# One_Square_Boy.net
KiCad netlist of a schematic drawn in EAGLE
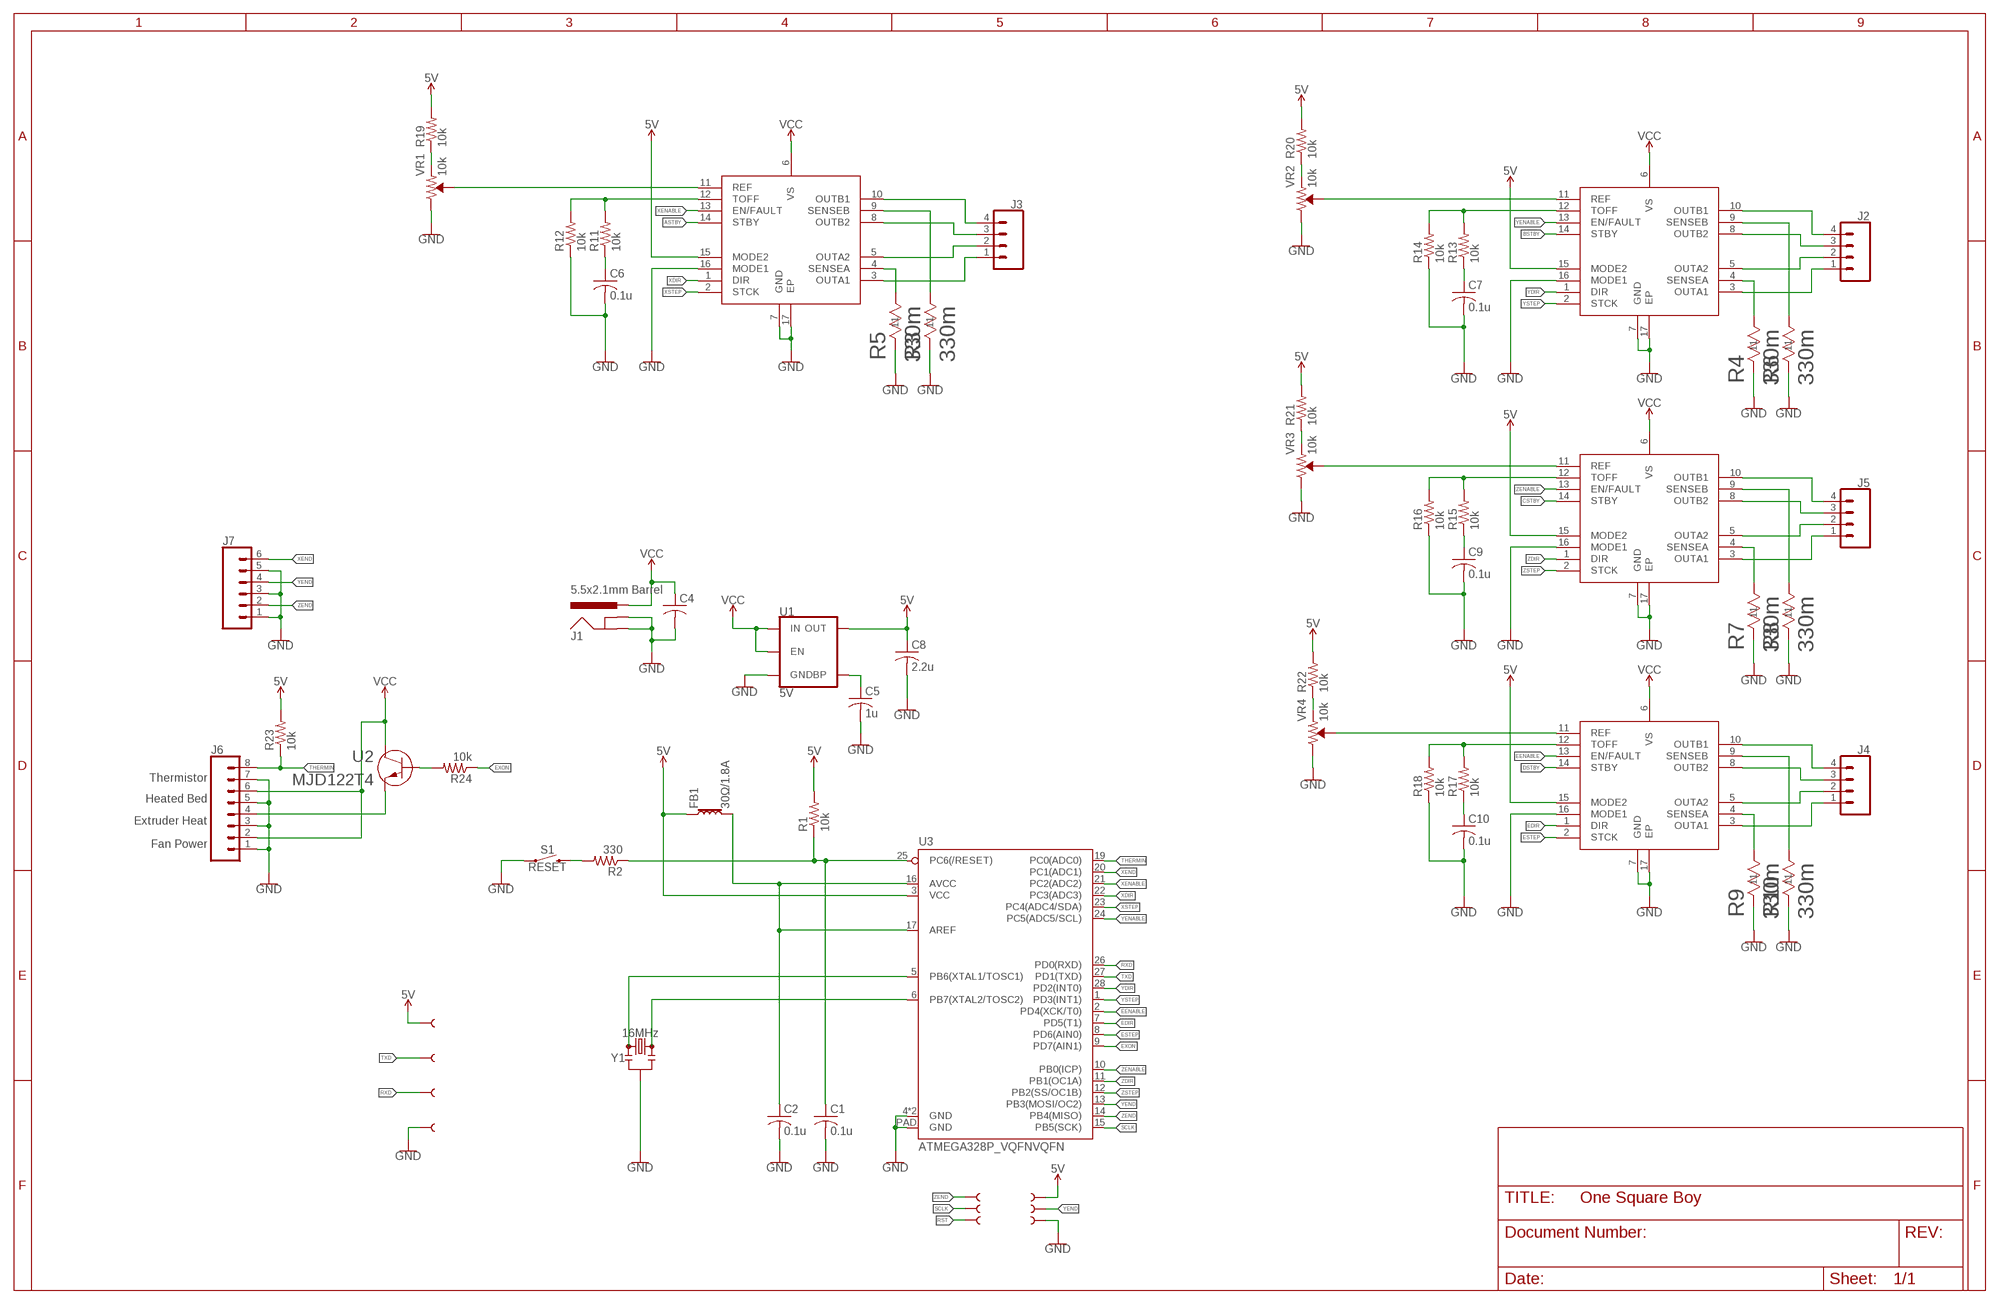
[diagram p0: schematic, sheet 1]

(export (version "E")
  (design (tool "Eeschema 10.0.6"))
  (components
    (comp (ref "C1")
      (value "0.1u")
      (footprint "eagle-import:C0402")
      (libsource (lib "eagle-import") (part "C-USC0402"))
    )
    (comp (ref "C2")
      (value "0.1u")
      (footprint "eagle-import:C0402")
      (libsource (lib "eagle-import") (part "C-USC0402"))
    )
    (comp (ref "C4")
      (value "C-USC1206")
      (footprint "eagle-import:C1206")
      (libsource (lib "eagle-import") (part "C-USC1206"))
    )
    (comp (ref "C5")
      (value "1u")
      (footprint "eagle-import:C0402")
      (libsource (lib "eagle-import") (part "C-USC0402"))
    )
    (comp (ref "C6")
      (value "0.1u")
      (footprint "eagle-import:C0402")
      (libsource (lib "eagle-import") (part "C-USC0402"))
    )
    (comp (ref "C7")
      (value "0.1u")
      (footprint "eagle-import:C0402")
      (libsource (lib "eagle-import") (part "C-USC0402"))
    )
    (comp (ref "C8")
      (value "2.2u")
      (footprint "eagle-import:C0402")
      (libsource (lib "eagle-import") (part "C-USC0402"))
    )
    (comp (ref "C9")
      (value "0.1u")
      (footprint "eagle-import:C0402")
      (libsource (lib "eagle-import") (part "C-USC0402"))
    )
    (comp (ref "C10")
      (value "0.1u")
      (footprint "eagle-import:C0402")
      (libsource (lib "eagle-import") (part "C-USC0402"))
    )
    (comp (ref "FB1")
      (value "30Ω/1.8A")
      (footprint "eagle-import:0603")
      (libsource (lib "eagle-import") (part "FERRITE_BEAD-0603"))
    )
    (comp (ref "J1")
      (value "5.5x2.1mm Barrel")
      (footprint "eagle-import:POWER_JACK_SMD")
      (libsource (lib "eagle-import") (part "POWER_JACKSMD"))
    )
    (comp (ref "J2")
      (value "CONN_04SMD2")
      (footprint "eagle-import:1X04_1MM_RA")
      (libsource (lib "eagle-import") (part "CONN_04SMD2"))
    )
    (comp (ref "J3")
      (value "CONN_04SMD2")
      (footprint "eagle-import:1X04_1MM_RA")
      (libsource (lib "eagle-import") (part "CONN_04SMD2"))
    )
    (comp (ref "J4")
      (value "CONN_04SMD2")
      (footprint "eagle-import:1X04_1MM_RA")
      (libsource (lib "eagle-import") (part "CONN_04SMD2"))
    )
    (comp (ref "J5")
      (value "CONN_04SMD2")
      (footprint "eagle-import:1X04_1MM_RA")
      (libsource (lib "eagle-import") (part "CONN_04SMD2"))
    )
    (comp (ref "J6")
      (value "CONN_08BM08B-SRSS-TB")
      (footprint "eagle-import:BM08B-SRSS-TB")
      (libsource (lib "eagle-import") (part "CONN_08BM08B-SRSS-TB"))
    )
    (comp (ref "J7")
      (value "CONN_06SMD-1MM")
      (footprint "eagle-import:1X06-1MM")
      (libsource (lib "eagle-import") (part "CONN_06SMD-1MM"))
    )
    (comp (ref "R1")
      (value "10k")
      (footprint "eagle-import:R0402")
      (libsource (lib "eagle-import") (part "R-US_R0402"))
    )
    (comp (ref "R2")
      (value "330")
      (footprint "eagle-import:R0402")
      (libsource (lib "eagle-import") (part "R-US_R0402"))
    )
    (comp (ref "R3")
      (value "330m")
      (footprint "eagle-import:RES_2012-L")
      (fields (field (name "MANUFACTURER_PART_NUMBER") "KRL2012EMR330FT5"))
      (libsource (lib "eagle-import") (part "KRL2012E-M-R330-F-T5RES_2012-L"))
    )
    (comp (ref "R4")
      (value "330m")
      (footprint "eagle-import:RES_2012-L")
      (fields (field (name "MANUFACTURER_PART_NUMBER") "KRL2012EMR330FT5"))
      (libsource (lib "eagle-import") (part "KRL2012E-M-R330-F-T5RES_2012-L"))
    )
    (comp (ref "R5")
      (value "330m")
      (footprint "eagle-import:RES_2012-L")
      (fields (field (name "MANUFACTURER_PART_NUMBER") "KRL2012EMR330FT5"))
      (libsource (lib "eagle-import") (part "KRL2012E-M-R330-F-T5RES_2012-L"))
    )
    (comp (ref "R6")
      (value "330m")
      (footprint "eagle-import:RES_2012-L")
      (fields (field (name "MANUFACTURER_PART_NUMBER") "KRL2012EMR330FT5"))
      (libsource (lib "eagle-import") (part "KRL2012E-M-R330-F-T5RES_2012-L"))
    )
    (comp (ref "R7")
      (value "330m")
      (footprint "eagle-import:RES_2012-L")
      (fields (field (name "MANUFACTURER_PART_NUMBER") "KRL2012EMR330FT5"))
      (libsource (lib "eagle-import") (part "KRL2012E-M-R330-F-T5RES_2012-L"))
    )
    (comp (ref "R8")
      (value "330m")
      (footprint "eagle-import:RES_2012-L")
      (fields (field (name "MANUFACTURER_PART_NUMBER") "KRL2012EMR330FT5"))
      (libsource (lib "eagle-import") (part "KRL2012E-M-R330-F-T5RES_2012-L"))
    )
    (comp (ref "R9")
      (value "330m")
      (footprint "eagle-import:RES_2012-L")
      (fields (field (name "MANUFACTURER_PART_NUMBER") "KRL2012EMR330FT5"))
      (libsource (lib "eagle-import") (part "KRL2012E-M-R330-F-T5RES_2012-L"))
    )
    (comp (ref "R10")
      (value "330m")
      (footprint "eagle-import:RES_2012-L")
      (fields (field (name "MANUFACTURER_PART_NUMBER") "KRL2012EMR330FT5"))
      (libsource (lib "eagle-import") (part "KRL2012E-M-R330-F-T5RES_2012-L"))
    )
    (comp (ref "R11")
      (value "10k")
      (footprint "eagle-import:R0402")
      (libsource (lib "eagle-import") (part "R-US_R0402"))
    )
    (comp (ref "R12")
      (value "10k")
      (footprint "eagle-import:R0402")
      (libsource (lib "eagle-import") (part "R-US_R0402"))
    )
    (comp (ref "R13")
      (value "10k")
      (footprint "eagle-import:R0402")
      (libsource (lib "eagle-import") (part "R-US_R0402"))
    )
    (comp (ref "R14")
      (value "10k")
      (footprint "eagle-import:R0402")
      (libsource (lib "eagle-import") (part "R-US_R0402"))
    )
    (comp (ref "R15")
      (value "10k")
      (footprint "eagle-import:R0402")
      (libsource (lib "eagle-import") (part "R-US_R0402"))
    )
    (comp (ref "R16")
      (value "10k")
      (footprint "eagle-import:R0402")
      (libsource (lib "eagle-import") (part "R-US_R0402"))
    )
    (comp (ref "R17")
      (value "10k")
      (footprint "eagle-import:R0402")
      (libsource (lib "eagle-import") (part "R-US_R0402"))
    )
    (comp (ref "R18")
      (value "10k")
      (footprint "eagle-import:R0402")
      (libsource (lib "eagle-import") (part "R-US_R0402"))
    )
    (comp (ref "R19")
      (value "10k")
      (footprint "eagle-import:R0402")
      (libsource (lib "eagle-import") (part "R-US_R0402"))
    )
    (comp (ref "R20")
      (value "10k")
      (footprint "eagle-import:R0402")
      (libsource (lib "eagle-import") (part "R-US_R0402"))
    )
    (comp (ref "R21")
      (value "10k")
      (footprint "eagle-import:R0402")
      (libsource (lib "eagle-import") (part "R-US_R0402"))
    )
    (comp (ref "R22")
      (value "10k")
      (footprint "eagle-import:R0402")
      (libsource (lib "eagle-import") (part "R-US_R0402"))
    )
    (comp (ref "R23")
      (value "10k")
      (footprint "eagle-import:R0402")
      (libsource (lib "eagle-import") (part "R-US_R0402"))
    )
    (comp (ref "R24")
      (value "10k")
      (footprint "eagle-import:R0402")
      (libsource (lib "eagle-import") (part "R-US_R0402"))
    )
    (comp (ref "S1")
      (value "RESET")
      (footprint "eagle-import:TACTILE_SWITCH_SMD_4.6X2.8MM")
      (libsource (lib "eagle-import") (part "MOMENTARY-SWITCH-SPST-SMD-4.6X2.8MM"))
    )
    (comp (ref "TP1")
      (value "TEST-POINT3X5")
      (footprint "eagle-import:PAD.03X.05")
      (libsource (lib "eagle-import") (part "TEST-POINT3X5"))
    )
    (comp (ref "TP2")
      (value "TEST-POINT3X5")
      (footprint "eagle-import:PAD.03X.05")
      (libsource (lib "eagle-import") (part "TEST-POINT3X5"))
    )
    (comp (ref "TP3")
      (value "TEST-POINT3X5")
      (footprint "eagle-import:PAD.03X.05")
      (libsource (lib "eagle-import") (part "TEST-POINT3X5"))
    )
    (comp (ref "TP4")
      (value "TEST-POINT3X5")
      (footprint "eagle-import:PAD.03X.05")
      (libsource (lib "eagle-import") (part "TEST-POINT3X5"))
    )
    (comp (ref "TP5")
      (value "TEST-POINT3X5")
      (footprint "eagle-import:PAD.03X.05")
      (libsource (lib "eagle-import") (part "TEST-POINT3X5"))
    )
    (comp (ref "TP6")
      (value "TEST-POINT3X5")
      (footprint "eagle-import:PAD.03X.05")
      (libsource (lib "eagle-import") (part "TEST-POINT3X5"))
    )
    (comp (ref "TP7")
      (value "TEST-POINT3X5")
      (footprint "eagle-import:PAD.03X.05")
      (libsource (lib "eagle-import") (part "TEST-POINT3X5"))
    )
    (comp (ref "TP8")
      (value "TEST-POINT3X5")
      (footprint "eagle-import:PAD.03X.05")
      (libsource (lib "eagle-import") (part "TEST-POINT3X5"))
    )
    (comp (ref "TP9")
      (value "TEST-POINT3X5")
      (footprint "eagle-import:PAD.03X.05")
      (libsource (lib "eagle-import") (part "TEST-POINT3X5"))
    )
    (comp (ref "TP10")
      (value "TEST-POINT3X5")
      (footprint "eagle-import:PAD.03X.05")
      (libsource (lib "eagle-import") (part "TEST-POINT3X5"))
    )
    (comp (ref "U$1")
      (value "STSPIN220")
      (footprint "eagle-import:QFN50P300X300X100-17N")
      (libsource (lib "eagle-import") (part "STSPIN220"))
    )
    (comp (ref "U$2")
      (value "STSPIN220")
      (footprint "eagle-import:QFN50P300X300X100-17N")
      (libsource (lib "eagle-import") (part "STSPIN220"))
    )
    (comp (ref "U$3")
      (value "STSPIN220")
      (footprint "eagle-import:QFN50P300X300X100-17N")
      (libsource (lib "eagle-import") (part "STSPIN220"))
    )
    (comp (ref "U$4")
      (value "STSPIN220")
      (footprint "eagle-import:QFN50P300X300X100-17N")
      (libsource (lib "eagle-import") (part "STSPIN220"))
    )
    (comp (ref "U1")
      (value "5V")
      (footprint "eagle-import:SOT23-5")
      (libsource (lib "eagle-import") (part "V_REG_MIC52055V"))
    )
    (comp (ref "U2")
      (value "MJD122T4")
      (footprint "eagle-import:DPAK")
      (libsource (lib "eagle-import") (part "MJD122T4"))
    )
    (comp (ref "U3")
      (value "ATMEGA328P_VQFNVQFN")
      (footprint "eagle-import:VQFN-28")
      (libsource (lib "eagle-import") (part "ATMEGA328P_VQFNVQFN"))
    )
    (comp (ref "VR1")
      (value "10k")
      (footprint "eagle-import:TRIMPOT-SMD-TC33X")
      (libsource (lib "eagle-import") (part "TRIMPOT-SMD-3MM-OPEN-1/10W-25%"))
    )
    (comp (ref "VR2")
      (value "10k")
      (footprint "eagle-import:TRIMPOT-SMD-TC33X")
      (libsource (lib "eagle-import") (part "TRIMPOT-SMD-3MM-OPEN-1/10W-25%"))
    )
    (comp (ref "VR3")
      (value "10k")
      (footprint "eagle-import:TRIMPOT-SMD-TC33X")
      (libsource (lib "eagle-import") (part "TRIMPOT-SMD-3MM-OPEN-1/10W-25%"))
    )
    (comp (ref "VR4")
      (value "10k")
      (footprint "eagle-import:TRIMPOT-SMD-TC33X")
      (libsource (lib "eagle-import") (part "TRIMPOT-SMD-3MM-OPEN-1/10W-25%"))
    )
    (comp (ref "Y1")
      (value "16MHz")
      (footprint "eagle-import:RESONATOR-SMD-3.2X1.3")
      (libsource (lib "eagle-import") (part "RESONATOR-16MHZSMD_3.2X1.3"))
    )
  )
  (nets
    (net (code "1") (name "5V") (class "Default")
      (node (ref "C8") (pin "1") (pinfunction "1_1") (pintype "passive"))
      (node (ref "FB1") (pin "1") (pinfunction "1_1") (pintype "passive"))
      (node (ref "R1") (pin "2") (pinfunction "2_2") (pintype "passive"))
      (node (ref "R19") (pin "2") (pinfunction "2_2") (pintype "passive"))
      (node (ref "R20") (pin "2") (pinfunction "2_2") (pintype "passive"))
      (node (ref "R21") (pin "2") (pinfunction "2_2") (pintype "passive"))
      (node (ref "R22") (pin "2") (pinfunction "2_2") (pintype "passive"))
      (node (ref "R23") (pin "2") (pinfunction "2_2") (pintype "passive"))
      (node (ref "TP10") (pin "P$1") (pinfunction "1_P$1") (pintype "bidirectional"))
      (node (ref "TP4") (pin "P$1") (pinfunction "1_P$1") (pintype "bidirectional"))
      (node (ref "U$1") (pin "15") (pinfunction "MODE2_15") (pintype "bidirectional"))
      (node (ref "U$2") (pin "15") (pinfunction "MODE2_15") (pintype "bidirectional"))
      (node (ref "U$3") (pin "15") (pinfunction "MODE2_15") (pintype "bidirectional"))
      (node (ref "U$4") (pin "15") (pinfunction "MODE2_15") (pintype "bidirectional"))
      (node (ref "U1") (pin "5") (pinfunction "OUT_5") (pintype "passive"))
      (node (ref "U3") (pin "3") (pinfunction "VCC_3") (pintype "bidirectional"))
    )
    (net (code "2") (name "ASTBY") (class "Default")
      (node (ref "U$1") (pin "14") (pinfunction "STBY_14") (pintype "bidirectional"))
    )
    (net (code "3") (name "BSTBY") (class "Default")
      (node (ref "U$2") (pin "14") (pinfunction "STBY_14") (pintype "bidirectional"))
    )
    (net (code "4") (name "CSTBY") (class "Default")
      (node (ref "U$3") (pin "14") (pinfunction "STBY_14") (pintype "bidirectional"))
    )
    (net (code "5") (name "DSTBY") (class "Default")
      (node (ref "U$4") (pin "14") (pinfunction "STBY_14") (pintype "bidirectional"))
    )
    (net (code "6") (name "EDIR") (class "Default")
      (node (ref "U$4") (pin "1") (pinfunction "DIR_1") (pintype "bidirectional"))
      (node (ref "U3") (pin "7") (pinfunction "PD5(T1)_7") (pintype "bidirectional"))
    )
    (net (code "7") (name "EENABLE") (class "Default")
      (node (ref "U$4") (pin "13") (pinfunction "EN/FAULT_13") (pintype "bidirectional"))
      (node (ref "U3") (pin "2") (pinfunction "PD4(XCK/T0)_2") (pintype "bidirectional"))
    )
    (net (code "8") (name "ESTEP") (class "Default")
      (node (ref "U$4") (pin "2") (pinfunction "STCK_2") (pintype "bidirectional"))
      (node (ref "U3") (pin "8") (pinfunction "PD6(AIN0)_8") (pintype "bidirectional"))
    )
    (net (code "9") (name "EXON") (class "Default")
      (node (ref "R24") (pin "1") (pinfunction "1_1") (pintype "passive"))
      (node (ref "U3") (pin "9") (pinfunction "PD7(AIN1)_9") (pintype "bidirectional"))
    )
    (net (code "10") (name "GND") (class "Default")
      (node (ref "C1") (pin "2") (pinfunction "2_2") (pintype "passive"))
      (node (ref "C10") (pin "2") (pinfunction "2_2") (pintype "passive"))
      (node (ref "C2") (pin "2") (pinfunction "2_2") (pintype "passive"))
      (node (ref "C4") (pin "2") (pinfunction "2_2") (pintype "passive"))
      (node (ref "C5") (pin "2") (pinfunction "2_2") (pintype "passive"))
      (node (ref "C6") (pin "2") (pinfunction "2_2") (pintype "passive"))
      (node (ref "C7") (pin "2") (pinfunction "2_2") (pintype "passive"))
      (node (ref "C8") (pin "2") (pinfunction "2_2") (pintype "passive"))
      (node (ref "C9") (pin "2") (pinfunction "2_2") (pintype "passive"))
      (node (ref "J1") (pin "GND") (pinfunction "GNDBREAK_GND") (pintype "bidirectional"))
      (node (ref "J1") (pin "P$4") (pinfunction "GND_P$4") (pintype "bidirectional"))
      (node (ref "J6") (pin "1") (pinfunction "1_1") (pintype "passive"))
      (node (ref "J6") (pin "3") (pinfunction "3_3") (pintype "passive"))
      (node (ref "J6") (pin "5") (pinfunction "5_5") (pintype "passive"))
      (node (ref "J6") (pin "7") (pinfunction "7_7") (pintype "passive"))
      (node (ref "J7") (pin "1") (pinfunction "1_1") (pintype "passive"))
      (node (ref "J7") (pin "3") (pinfunction "3_3") (pintype "passive"))
      (node (ref "J7") (pin "5") (pinfunction "5_5") (pintype "passive"))
      (node (ref "R10") (pin "1") (pinfunction "11_1") (pintype "passive"))
      (node (ref "R12") (pin "1") (pinfunction "1_1") (pintype "passive"))
      (node (ref "R14") (pin "1") (pinfunction "1_1") (pintype "passive"))
      (node (ref "R16") (pin "1") (pinfunction "1_1") (pintype "passive"))
      (node (ref "R18") (pin "1") (pinfunction "1_1") (pintype "passive"))
      (node (ref "R3") (pin "1") (pinfunction "11_1") (pintype "passive"))
      (node (ref "R4") (pin "1") (pinfunction "11_1") (pintype "passive"))
      (node (ref "R5") (pin "1") (pinfunction "11_1") (pintype "passive"))
      (node (ref "R6") (pin "1") (pinfunction "11_1") (pintype "passive"))
      (node (ref "R7") (pin "1") (pinfunction "11_1") (pintype "passive"))
      (node (ref "R8") (pin "1") (pinfunction "11_1") (pintype "passive"))
      (node (ref "R9") (pin "1") (pinfunction "11_1") (pintype "passive"))
      (node (ref "S1") (pin "1") (pinfunction "1_1") (pintype "passive"))
      (node (ref "S1") (pin "2") (pinfunction "1_2") (pintype "passive"))
      (node (ref "TP6") (pin "P$1") (pinfunction "1_P$1") (pintype "bidirectional"))
      (node (ref "TP7") (pin "P$1") (pinfunction "1_P$1") (pintype "bidirectional"))
      (node (ref "U$1") (pin "16") (pinfunction "MODE1_16") (pintype "bidirectional"))
      (node (ref "U$1") (pin "17") (pinfunction "EP_17") (pintype "bidirectional"))
      (node (ref "U$1") (pin "7") (pinfunction "GND_7") (pintype "bidirectional"))
      (node (ref "U$2") (pin "16") (pinfunction "MODE1_16") (pintype "bidirectional"))
      (node (ref "U$2") (pin "17") (pinfunction "EP_17") (pintype "bidirectional"))
      (node (ref "U$2") (pin "7") (pinfunction "GND_7") (pintype "bidirectional"))
      (node (ref "U$3") (pin "16") (pinfunction "MODE1_16") (pintype "bidirectional"))
      (node (ref "U$3") (pin "17") (pinfunction "EP_17") (pintype "bidirectional"))
      (node (ref "U$3") (pin "7") (pinfunction "GND_7") (pintype "bidirectional"))
      (node (ref "U$4") (pin "16") (pinfunction "MODE1_16") (pintype "bidirectional"))
      (node (ref "U$4") (pin "17") (pinfunction "EP_17") (pintype "bidirectional"))
      (node (ref "U$4") (pin "7") (pinfunction "GND_7") (pintype "bidirectional"))
      (node (ref "U1") (pin "2") (pinfunction "GND_2") (pintype "input"))
      (node (ref "U3") (pin "18") (pinfunction "GND_18") (pintype "bidirectional"))
      (node (ref "U3") (pin "4") (pinfunction "GND_4") (pintype "bidirectional"))
      (node (ref "U3") (pin "PAD") (pinfunction "GND_PAD") (pintype "bidirectional"))
      (node (ref "VR1") (pin "1") (pinfunction "CW_1") (pintype "passive"))
      (node (ref "VR2") (pin "1") (pinfunction "CW_1") (pintype "passive"))
      (node (ref "VR3") (pin "1") (pinfunction "CW_1") (pintype "passive"))
      (node (ref "VR4") (pin "1") (pinfunction "CW_1") (pintype "passive"))
      (node (ref "Y1") (pin "2") (pinfunction "2_2") (pintype "passive"))
    )
    (net (code "11") (name "Net-(C6-Pad1)") (class "Default")
      (node (ref "C6") (pin "1") (pinfunction "1_1") (pintype "passive"))
      (node (ref "R11") (pin "1") (pinfunction "1_1") (pintype "passive"))
    )
    (net (code "12") (name "Net-(C7-Pad1)") (class "Default")
      (node (ref "C7") (pin "1") (pinfunction "1_1") (pintype "passive"))
      (node (ref "R13") (pin "1") (pinfunction "1_1") (pintype "passive"))
    )
    (net (code "13") (name "Net-(C9-Pad1)") (class "Default")
      (node (ref "C9") (pin "1") (pinfunction "1_1") (pintype "passive"))
      (node (ref "R15") (pin "1") (pinfunction "1_1") (pintype "passive"))
    )
    (net (code "14") (name "Net-(C10-Pad1)") (class "Default")
      (node (ref "C10") (pin "1") (pinfunction "1_1") (pintype "passive"))
      (node (ref "R17") (pin "1") (pinfunction "1_1") (pintype "passive"))
    )
    (net (code "15") (name "Net-(R2-Pad2)") (class "Default")
      (node (ref "R2") (pin "2") (pinfunction "2_2") (pintype "passive"))
      (node (ref "S1") (pin "3") (pinfunction "2_3") (pintype "passive"))
      (node (ref "S1") (pin "4") (pinfunction "2_4") (pintype "passive"))
    )
    (net (code "16") (name "Net-(R3-22)") (class "Default")
      (node (ref "R3") (pin "2") (pinfunction "22_2") (pintype "passive"))
      (node (ref "U$1") (pin "9") (pinfunction "SENSEB_9") (pintype "bidirectional"))
    )
    (net (code "17") (name "Net-(R4-22)") (class "Default")
      (node (ref "R4") (pin "2") (pinfunction "22_2") (pintype "passive"))
      (node (ref "U$2") (pin "4") (pinfunction "SENSEA_4") (pintype "bidirectional"))
    )
    (net (code "18") (name "Net-(R5-22)") (class "Default")
      (node (ref "R5") (pin "2") (pinfunction "22_2") (pintype "passive"))
      (node (ref "U$1") (pin "4") (pinfunction "SENSEA_4") (pintype "bidirectional"))
    )
    (net (code "19") (name "Net-(R6-22)") (class "Default")
      (node (ref "R6") (pin "2") (pinfunction "22_2") (pintype "passive"))
      (node (ref "U$2") (pin "9") (pinfunction "SENSEB_9") (pintype "bidirectional"))
    )
    (net (code "20") (name "Net-(R7-22)") (class "Default")
      (node (ref "R7") (pin "2") (pinfunction "22_2") (pintype "passive"))
      (node (ref "U$3") (pin "4") (pinfunction "SENSEA_4") (pintype "bidirectional"))
    )
    (net (code "21") (name "Net-(R8-22)") (class "Default")
      (node (ref "R8") (pin "2") (pinfunction "22_2") (pintype "passive"))
      (node (ref "U$3") (pin "9") (pinfunction "SENSEB_9") (pintype "bidirectional"))
    )
    (net (code "22") (name "Net-(R9-22)") (class "Default")
      (node (ref "R9") (pin "2") (pinfunction "22_2") (pintype "passive"))
      (node (ref "U$4") (pin "4") (pinfunction "SENSEA_4") (pintype "bidirectional"))
    )
    (net (code "23") (name "Net-(R10-22)") (class "Default")
      (node (ref "R10") (pin "2") (pinfunction "22_2") (pintype "passive"))
      (node (ref "U$4") (pin "9") (pinfunction "SENSEB_9") (pintype "bidirectional"))
    )
    (net (code "24") (name "Net-(U$1-OUTA1)") (class "Default")
      (node (ref "J3") (pin "1") (pinfunction "1_1") (pintype "passive"))
      (node (ref "U$1") (pin "3") (pinfunction "OUTA1_3") (pintype "bidirectional"))
    )
    (net (code "25") (name "Net-(U$1-OUTA2)") (class "Default")
      (node (ref "J3") (pin "2") (pinfunction "2_2") (pintype "passive"))
      (node (ref "U$1") (pin "5") (pinfunction "OUTA2_5") (pintype "bidirectional"))
    )
    (net (code "26") (name "Net-(U$1-OUTB1)") (class "Default")
      (node (ref "J3") (pin "4") (pinfunction "4_4") (pintype "passive"))
      (node (ref "U$1") (pin "10") (pinfunction "OUTB1_10") (pintype "bidirectional"))
    )
    (net (code "27") (name "Net-(U$1-OUTB2)") (class "Default")
      (node (ref "J3") (pin "3") (pinfunction "3_3") (pintype "passive"))
      (node (ref "U$1") (pin "8") (pinfunction "OUTB2_8") (pintype "bidirectional"))
    )
    (net (code "28") (name "Net-(U$1-REF)") (class "Default")
      (node (ref "U$1") (pin "11") (pinfunction "REF_11") (pintype "bidirectional"))
      (node (ref "VR1") (pin "2") (pinfunction "WIPER_2") (pintype "passive"))
    )
    (net (code "29") (name "Net-(U$1-TOFF)") (class "Default")
      (node (ref "R11") (pin "2") (pinfunction "2_2") (pintype "passive"))
      (node (ref "R12") (pin "2") (pinfunction "2_2") (pintype "passive"))
      (node (ref "U$1") (pin "12") (pinfunction "TOFF_12") (pintype "bidirectional"))
    )
    (net (code "30") (name "Net-(U$2-OUTA1)") (class "Default")
      (node (ref "J2") (pin "1") (pinfunction "1_1") (pintype "passive"))
      (node (ref "U$2") (pin "3") (pinfunction "OUTA1_3") (pintype "bidirectional"))
    )
    (net (code "31") (name "Net-(U$2-OUTA2)") (class "Default")
      (node (ref "J2") (pin "2") (pinfunction "2_2") (pintype "passive"))
      (node (ref "U$2") (pin "5") (pinfunction "OUTA2_5") (pintype "bidirectional"))
    )
    (net (code "32") (name "Net-(U$2-OUTB1)") (class "Default")
      (node (ref "J2") (pin "4") (pinfunction "4_4") (pintype "passive"))
      (node (ref "U$2") (pin "10") (pinfunction "OUTB1_10") (pintype "bidirectional"))
    )
    (net (code "33") (name "Net-(U$2-OUTB2)") (class "Default")
      (node (ref "J2") (pin "3") (pinfunction "3_3") (pintype "passive"))
      (node (ref "U$2") (pin "8") (pinfunction "OUTB2_8") (pintype "bidirectional"))
    )
    (net (code "34") (name "Net-(U$2-REF)") (class "Default")
      (node (ref "U$2") (pin "11") (pinfunction "REF_11") (pintype "bidirectional"))
      (node (ref "VR2") (pin "2") (pinfunction "WIPER_2") (pintype "passive"))
    )
    (net (code "35") (name "Net-(U$2-TOFF)") (class "Default")
      (node (ref "R13") (pin "2") (pinfunction "2_2") (pintype "passive"))
      (node (ref "R14") (pin "2") (pinfunction "2_2") (pintype "passive"))
      (node (ref "U$2") (pin "12") (pinfunction "TOFF_12") (pintype "bidirectional"))
    )
    (net (code "36") (name "Net-(U$3-OUTA1)") (class "Default")
      (node (ref "J5") (pin "1") (pinfunction "1_1") (pintype "passive"))
      (node (ref "U$3") (pin "3") (pinfunction "OUTA1_3") (pintype "bidirectional"))
    )
    (net (code "37") (name "Net-(U$3-OUTA2)") (class "Default")
      (node (ref "J5") (pin "2") (pinfunction "2_2") (pintype "passive"))
      (node (ref "U$3") (pin "5") (pinfunction "OUTA2_5") (pintype "bidirectional"))
    )
    (net (code "38") (name "Net-(U$3-OUTB1)") (class "Default")
      (node (ref "J5") (pin "4") (pinfunction "4_4") (pintype "passive"))
      (node (ref "U$3") (pin "10") (pinfunction "OUTB1_10") (pintype "bidirectional"))
    )
    (net (code "39") (name "Net-(U$3-OUTB2)") (class "Default")
      (node (ref "J5") (pin "3") (pinfunction "3_3") (pintype "passive"))
      (node (ref "U$3") (pin "8") (pinfunction "OUTB2_8") (pintype "bidirectional"))
    )
    (net (code "40") (name "Net-(U$3-REF)") (class "Default")
      (node (ref "U$3") (pin "11") (pinfunction "REF_11") (pintype "bidirectional"))
      (node (ref "VR3") (pin "2") (pinfunction "WIPER_2") (pintype "passive"))
    )
    (net (code "41") (name "Net-(U$3-TOFF)") (class "Default")
      (node (ref "R15") (pin "2") (pinfunction "2_2") (pintype "passive"))
      (node (ref "R16") (pin "2") (pinfunction "2_2") (pintype "passive"))
      (node (ref "U$3") (pin "12") (pinfunction "TOFF_12") (pintype "bidirectional"))
    )
    (net (code "42") (name "Net-(U$4-OUTA1)") (class "Default")
      (node (ref "J4") (pin "1") (pinfunction "1_1") (pintype "passive"))
      (node (ref "U$4") (pin "3") (pinfunction "OUTA1_3") (pintype "bidirectional"))
    )
    (net (code "43") (name "Net-(U$4-OUTA2)") (class "Default")
      (node (ref "J4") (pin "2") (pinfunction "2_2") (pintype "passive"))
      (node (ref "U$4") (pin "5") (pinfunction "OUTA2_5") (pintype "bidirectional"))
    )
    (net (code "44") (name "Net-(U$4-OUTB1)") (class "Default")
      (node (ref "J4") (pin "4") (pinfunction "4_4") (pintype "passive"))
      (node (ref "U$4") (pin "10") (pinfunction "OUTB1_10") (pintype "bidirectional"))
    )
    (net (code "45") (name "Net-(U$4-OUTB2)") (class "Default")
      (node (ref "J4") (pin "3") (pinfunction "3_3") (pintype "passive"))
      (node (ref "U$4") (pin "8") (pinfunction "OUTB2_8") (pintype "bidirectional"))
    )
    (net (code "46") (name "Net-(U$4-REF)") (class "Default")
      (node (ref "U$4") (pin "11") (pinfunction "REF_11") (pintype "bidirectional"))
      (node (ref "VR4") (pin "2") (pinfunction "WIPER_2") (pintype "passive"))
    )
    (net (code "47") (name "Net-(U$4-TOFF)") (class "Default")
      (node (ref "R17") (pin "2") (pinfunction "2_2") (pintype "passive"))
      (node (ref "R18") (pin "2") (pinfunction "2_2") (pintype "passive"))
      (node (ref "U$4") (pin "12") (pinfunction "TOFF_12") (pintype "bidirectional"))
    )
    (net (code "48") (name "Net-(U1-BP)") (class "Default")
      (node (ref "C5") (pin "1") (pinfunction "1_1") (pintype "passive"))
      (node (ref "U1") (pin "4") (pinfunction "BP_4") (pintype "input"))
    )
    (net (code "49") (name "Net-(U2-B1)") (class "Default")
      (node (ref "R24") (pin "2") (pinfunction "2_2") (pintype "passive"))
      (node (ref "U2") (pin "1") (pinfunction "B1_1") (pintype "passive"))
    )
    (net (code "50") (name "Net-(U2-E2)") (class "Default")
      (node (ref "J6") (pin "4") (pinfunction "4_4") (pintype "passive"))
      (node (ref "U2") (pin "2") (pinfunction "E2_2") (pintype "passive"))
    )
    (net (code "51") (name "Net-(U3-AREF)") (class "Default")
      (node (ref "C2") (pin "1") (pinfunction "1_1") (pintype "passive"))
      (node (ref "FB1") (pin "2") (pinfunction "2_2") (pintype "passive"))
      (node (ref "U3") (pin "16") (pinfunction "AVCC_16") (pintype "bidirectional"))
      (node (ref "U3") (pin "17") (pinfunction "AREF_17") (pintype "bidirectional"))
    )
    (net (code "52") (name "Net-(U3-PB6(XTAL1{slash}TOSC1))") (class "Default")
      (node (ref "U3") (pin "5") (pinfunction "PB6(XTAL1/TOSC1)_5") (pintype "bidirectional"))
      (node (ref "Y1") (pin "1") (pinfunction "1_1") (pintype "passive"))
    )
    (net (code "53") (name "Net-(U3-PB7(XTAL2{slash}TOSC2))") (class "Default")
      (node (ref "U3") (pin "6") (pinfunction "PB7(XTAL2/TOSC2)_6") (pintype "bidirectional"))
      (node (ref "Y1") (pin "3") (pinfunction "3_3") (pintype "passive"))
    )
    (net (code "54") (name "Net-(VR1-CCW)") (class "Default")
      (node (ref "R19") (pin "1") (pinfunction "1_1") (pintype "passive"))
      (node (ref "VR1") (pin "3") (pinfunction "CCW_3") (pintype "passive"))
    )
    (net (code "55") (name "Net-(VR2-CCW)") (class "Default")
      (node (ref "R20") (pin "1") (pinfunction "1_1") (pintype "passive"))
      (node (ref "VR2") (pin "3") (pinfunction "CCW_3") (pintype "passive"))
    )
    (net (code "56") (name "Net-(VR3-CCW)") (class "Default")
      (node (ref "R21") (pin "1") (pinfunction "1_1") (pintype "passive"))
      (node (ref "VR3") (pin "3") (pinfunction "CCW_3") (pintype "passive"))
    )
    (net (code "57") (name "Net-(VR4-CCW)") (class "Default")
      (node (ref "R22") (pin "1") (pinfunction "1_1") (pintype "passive"))
      (node (ref "VR4") (pin "3") (pinfunction "CCW_3") (pintype "passive"))
    )
    (net (code "58") (name "RST") (class "Default")
      (node (ref "C1") (pin "1") (pinfunction "1_1") (pintype "passive"))
      (node (ref "R1") (pin "1") (pinfunction "1_1") (pintype "passive"))
      (node (ref "R2") (pin "1") (pinfunction "1_1") (pintype "passive"))
      (node (ref "TP3") (pin "P$1") (pinfunction "1_P$1") (pintype "bidirectional"))
      (node (ref "U3") (pin "25") (pinfunction "PC6(/RESET)_25") (pintype "bidirectional"))
    )
    (net (code "59") (name "RXD") (class "Default")
      (node (ref "TP8") (pin "P$1") (pinfunction "1_P$1") (pintype "bidirectional"))
      (node (ref "U3") (pin "26") (pinfunction "PD0(RXD)_26") (pintype "bidirectional"))
    )
    (net (code "60") (name "SCLK") (class "Default")
      (node (ref "TP2") (pin "P$1") (pinfunction "1_P$1") (pintype "bidirectional"))
      (node (ref "U3") (pin "15") (pinfunction "PB5(SCK)_15") (pintype "bidirectional"))
    )
    (net (code "61") (name "THERMIN") (class "Default")
      (node (ref "J6") (pin "8") (pinfunction "8_8") (pintype "passive"))
      (node (ref "R23") (pin "1") (pinfunction "1_1") (pintype "passive"))
      (node (ref "U3") (pin "19") (pinfunction "PC0(ADC0)_19") (pintype "bidirectional"))
    )
    (net (code "62") (name "TXD") (class "Default")
      (node (ref "TP9") (pin "P$1") (pinfunction "1_P$1") (pintype "bidirectional"))
      (node (ref "U3") (pin "27") (pinfunction "PD1(TXD)_27") (pintype "bidirectional"))
    )
    (net (code "63") (name "VCC") (class "Default")
      (node (ref "C4") (pin "1") (pinfunction "1_1") (pintype "passive"))
      (node (ref "J1") (pin "VIN0") (pinfunction "PWR_VIN0") (pintype "bidirectional"))
      (node (ref "J6") (pin "2") (pinfunction "2_2") (pintype "passive"))
      (node (ref "J6") (pin "6") (pinfunction "6_6") (pintype "passive"))
      (node (ref "U$1") (pin "6") (pinfunction "VS_6") (pintype "bidirectional"))
      (node (ref "U$2") (pin "6") (pinfunction "VS_6") (pintype "bidirectional"))
      (node (ref "U$3") (pin "6") (pinfunction "VS_6") (pintype "bidirectional"))
      (node (ref "U$4") (pin "6") (pinfunction "VS_6") (pintype "bidirectional"))
      (node (ref "U1") (pin "1") (pinfunction "IN_1") (pintype "input"))
      (node (ref "U1") (pin "3") (pinfunction "EN_3") (pintype "input"))
      (node (ref "U2") (pin "3") (pinfunction "C3_3") (pintype "passive"))
    )
    (net (code "64") (name "XDIR") (class "Default")
      (node (ref "U$1") (pin "1") (pinfunction "DIR_1") (pintype "bidirectional"))
      (node (ref "U3") (pin "22") (pinfunction "PC3(ADC3)_22") (pintype "bidirectional"))
    )
    (net (code "65") (name "XENABLE") (class "Default")
      (node (ref "U$1") (pin "13") (pinfunction "EN/FAULT_13") (pintype "bidirectional"))
      (node (ref "U3") (pin "21") (pinfunction "PC2(ADC2)_21") (pintype "bidirectional"))
    )
    (net (code "66") (name "XEND") (class "Default")
      (node (ref "J7") (pin "6") (pinfunction "6_6") (pintype "passive"))
      (node (ref "U3") (pin "20") (pinfunction "PC1(ADC1)_20") (pintype "bidirectional"))
    )
    (net (code "67") (name "XSTEP") (class "Default")
      (node (ref "U$1") (pin "2") (pinfunction "STCK_2") (pintype "bidirectional"))
      (node (ref "U3") (pin "23") (pinfunction "PC4(ADC4/SDA)_23") (pintype "bidirectional"))
    )
    (net (code "68") (name "YDIR") (class "Default")
      (node (ref "U$2") (pin "1") (pinfunction "DIR_1") (pintype "bidirectional"))
      (node (ref "U3") (pin "28") (pinfunction "PD2(INT0)_28") (pintype "bidirectional"))
    )
    (net (code "69") (name "YENABLE") (class "Default")
      (node (ref "U$2") (pin "13") (pinfunction "EN/FAULT_13") (pintype "bidirectional"))
      (node (ref "U3") (pin "24") (pinfunction "PC5(ADC5/SCL)_24") (pintype "bidirectional"))
    )
    (net (code "70") (name "YEND") (class "Default")
      (node (ref "J7") (pin "4") (pinfunction "4_4") (pintype "passive"))
      (node (ref "TP5") (pin "P$1") (pinfunction "1_P$1") (pintype "bidirectional"))
      (node (ref "U3") (pin "13") (pinfunction "PB3(MOSI/OC2)_13") (pintype "bidirectional"))
    )
    (net (code "71") (name "YSTEP") (class "Default")
      (node (ref "U$2") (pin "2") (pinfunction "STCK_2") (pintype "bidirectional"))
      (node (ref "U3") (pin "1") (pinfunction "PD3(INT1)_1") (pintype "bidirectional"))
    )
    (net (code "72") (name "ZDIR") (class "Default")
      (node (ref "U$3") (pin "1") (pinfunction "DIR_1") (pintype "bidirectional"))
      (node (ref "U3") (pin "11") (pinfunction "PB1(OC1A)_11") (pintype "bidirectional"))
    )
    (net (code "73") (name "ZENABLE") (class "Default")
      (node (ref "U$3") (pin "13") (pinfunction "EN/FAULT_13") (pintype "bidirectional"))
      (node (ref "U3") (pin "10") (pinfunction "PB0(ICP)_10") (pintype "bidirectional"))
    )
    (net (code "74") (name "ZEND") (class "Default")
      (node (ref "J7") (pin "2") (pinfunction "2_2") (pintype "passive"))
      (node (ref "TP1") (pin "P$1") (pinfunction "1_P$1") (pintype "bidirectional"))
      (node (ref "U3") (pin "14") (pinfunction "PB4(MISO)_14") (pintype "bidirectional"))
    )
    (net (code "75") (name "ZSTEP") (class "Default")
      (node (ref "U$3") (pin "2") (pinfunction "STCK_2") (pintype "bidirectional"))
      (node (ref "U3") (pin "12") (pinfunction "PB2(SS/OC1B)_12") (pintype "bidirectional"))
    )
  )
)
